# MaPan.net
KiCad netlist of a schematic drawn in Altium Designer
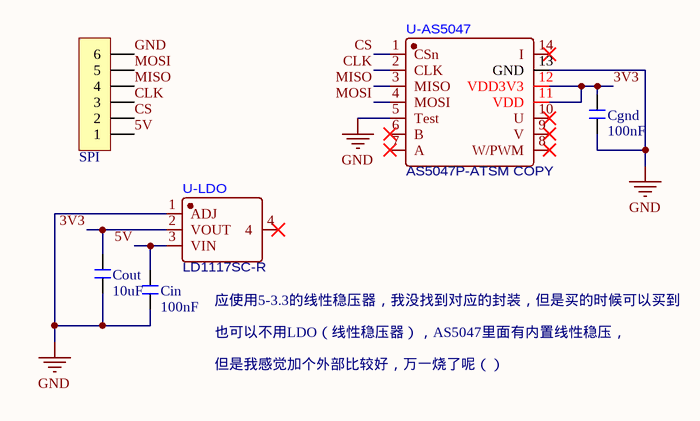
[diagram p0: MaPan.SchDoc]

(export (version "E")
  (design (tool "Eeschema 10.0.6"))
  (components
    (comp (ref "Cgnd")
      (value "100nF")
      (footprint "C 0603_M")
      (description "贴片电容")
      (libsource (lib "01 - 电容-电阻-电感") (part "C"))
    )
    (comp (ref "Cin")
      (value "100nF")
      (footprint "C 0603_M")
      (description "贴片电容")
      (libsource (lib "01 - 电容-电阻-电感") (part "C"))
    )
    (comp (ref "Cout")
      (value "10uF")
      (footprint "C 0603_M")
      (description "贴片电容")
      (libsource (lib "01 - 电容-电阻-电感") (part "C"))
    )
    (comp (ref "SPI")
      (value "HDR-1X6")
      (footprint "GH1.25-WS-6P")
      (description "6P接插件")
      (libsource (lib "16 - 接插件-脚距1.5mm") (part "Header 6"))
    )
    (comp (ref "U-AS5047")
      (value "AS5047P-ATSM COPY")
      (footprint "TSSOP-14_L5.0-W4.4-P0.65-LS6.4-BL")
      (libsource (lib "AS5047P") (part "AS5047P-ATSM COPY"))
    )
    (comp (ref "U-LDO")
      (value "LD1117SC-R")
      (footprint "SOT-223-3_L6.5-W3.4-P2.30-LS7.0-BR")
      (libsource (lib "LDO1117") (part "LD1117SC-R"))
    )
  )
  (nets
    (net (code "1") (name "/3V3") (class "Default")
      (node (ref "Cgnd") (pin "2") (pinfunction "2_2") (pintype "passive"))
      (node (ref "Cout") (pin "2") (pinfunction "2_2") (pintype "passive"))
      (node (ref "U-AS5047") (pin "11") (pinfunction "VDD_11") (pintype "passive"))
      (node (ref "U-AS5047") (pin "12") (pinfunction "VDD3V3_12") (pintype "passive"))
      (node (ref "U-LDO") (pin "2") (pinfunction "VOUT_2") (pintype "passive"))
    )
    (net (code "2") (name "/5V") (class "Default")
      (node (ref "Cin") (pin "2") (pinfunction "2_2") (pintype "passive"))
      (node (ref "SPI") (pin "1") (pinfunction "1_1") (pintype "passive"))
      (node (ref "U-LDO") (pin "3") (pinfunction "VIN_3") (pintype "passive"))
    )
    (net (code "3") (name "/CLK") (class "Default")
      (node (ref "SPI") (pin "3") (pinfunction "3_3") (pintype "passive"))
      (node (ref "U-AS5047") (pin "2") (pinfunction "CLK_2") (pintype "passive"))
    )
    (net (code "4") (name "/CS") (class "Default")
      (node (ref "SPI") (pin "2") (pinfunction "2_2") (pintype "passive"))
      (node (ref "U-AS5047") (pin "1") (pinfunction "CSn_1") (pintype "passive"))
    )
    (net (code "5") (name "/MISO") (class "Default")
      (node (ref "SPI") (pin "4") (pinfunction "4_4") (pintype "passive"))
      (node (ref "U-AS5047") (pin "3") (pinfunction "MISO_3") (pintype "passive"))
    )
    (net (code "6") (name "/MOSI") (class "Default")
      (node (ref "SPI") (pin "5") (pinfunction "5_5") (pintype "passive"))
      (node (ref "U-AS5047") (pin "4") (pinfunction "MOSI_4") (pintype "passive"))
    )
    (net (code "7") (name "GND") (class "Default")
      (node (ref "Cgnd") (pin "1") (pinfunction "1_1") (pintype "passive"))
      (node (ref "Cin") (pin "1") (pinfunction "1_1") (pintype "passive"))
      (node (ref "Cout") (pin "1") (pinfunction "1_1") (pintype "passive"))
      (node (ref "SPI") (pin "6") (pinfunction "6_6") (pintype "passive"))
      (node (ref "U-AS5047") (pin "13") (pinfunction "GND_13") (pintype "passive"))
      (node (ref "U-AS5047") (pin "5") (pinfunction "Test_5") (pintype "passive"))
      (node (ref "U-LDO") (pin "1") (pinfunction "ADJ_1") (pintype "passive"))
    )
    (net (code "8") (name "unconnected-(U-AS5047-A-Pad7)") (class "Default")
      (node (ref "U-AS5047") (pin "7") (pinfunction "A_7") (pintype "passive+no_connect"))
    )
    (net (code "9") (name "unconnected-(U-AS5047-B-Pad6)") (class "Default")
      (node (ref "U-AS5047") (pin "6") (pinfunction "B_6") (pintype "passive+no_connect"))
    )
    (net (code "10") (name "unconnected-(U-AS5047-I-Pad14)") (class "Default")
      (node (ref "U-AS5047") (pin "14") (pinfunction "I_14") (pintype "passive+no_connect"))
    )
    (net (code "11") (name "unconnected-(U-AS5047-U-Pad10)") (class "Default")
      (node (ref "U-AS5047") (pin "10") (pinfunction "U_10") (pintype "passive+no_connect"))
    )
    (net (code "12") (name "unconnected-(U-AS5047-V-Pad9)") (class "Default")
      (node (ref "U-AS5047") (pin "9") (pinfunction "V_9") (pintype "passive+no_connect"))
    )
    (net (code "13") (name "unconnected-(U-AS5047-W{slash}PWM-Pad8)") (class "Default")
      (node (ref "U-AS5047") (pin "8") (pinfunction "W/PWM_8") (pintype "passive+no_connect"))
    )
    (net (code "14") (name "unconnected-(U-LDO-Pad4)") (class "Default")
      (node (ref "U-LDO") (pin "4") (pinfunction "4_4") (pintype "passive+no_connect"))
    )
  )
)
